# design.net
KiCad netlist of a schematic drawn in EAGLE
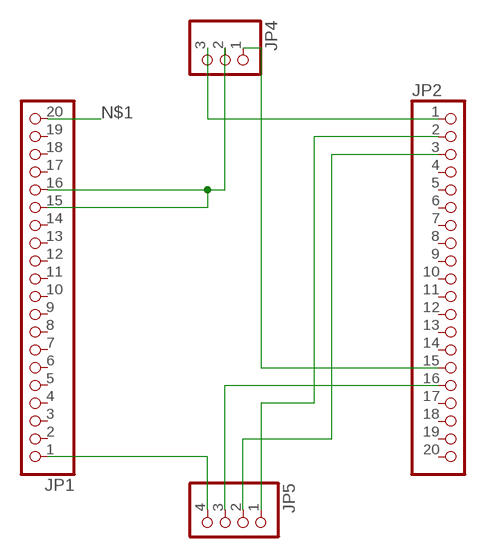
[diagram p0: schematic, sheet 1]

(export (version "E")
  (design (tool "Eeschema 10.0.6"))
  (components
    (comp (ref "JP1")
      (value "PINHD-1X20")
      (footprint "eagle-import:1X20")
      (libsource (lib "eagle-import") (part "PINHD-1X20"))
    )
    (comp (ref "JP2")
      (value "PINHD-1X20")
      (footprint "eagle-import:1X20")
      (libsource (lib "eagle-import") (part "PINHD-1X20"))
    )
    (comp (ref "JP4")
      (value "PINHD-1X3")
      (footprint "eagle-import:1X03")
      (libsource (lib "eagle-import") (part "PINHD-1X3"))
    )
    (comp (ref "JP5")
      (value "PINHD-1X4")
      (footprint "eagle-import:1X04")
      (libsource (lib "eagle-import") (part "PINHD-1X4"))
    )
  )
  (nets
    (net (code "1") (name "/N$1") (class "Default")
      (node (ref "JP1") (pin "20") (pinfunction "20_20") (pintype "passive"))
    )
    (net (code "2") (name "Net-(JP1-Pad1)") (class "Default")
      (node (ref "JP1") (pin "1") (pinfunction "1_1") (pintype "passive"))
      (node (ref "JP5") (pin "4") (pinfunction "4_4") (pintype "passive"))
    )
    (net (code "3") (name "Net-(JP1-Pad15)") (class "Default")
      (node (ref "JP1") (pin "15") (pinfunction "15_15") (pintype "passive"))
      (node (ref "JP1") (pin "16") (pinfunction "16_16") (pintype "passive"))
      (node (ref "JP4") (pin "2") (pinfunction "2_2") (pintype "passive"))
    )
    (net (code "4") (name "Net-(JP2-Pad1)") (class "Default")
      (node (ref "JP2") (pin "1") (pinfunction "1_1") (pintype "passive"))
      (node (ref "JP4") (pin "3") (pinfunction "3_3") (pintype "passive"))
    )
    (net (code "5") (name "Net-(JP2-Pad2)") (class "Default")
      (node (ref "JP2") (pin "2") (pinfunction "2_2") (pintype "passive"))
      (node (ref "JP5") (pin "1") (pinfunction "1_1") (pintype "passive"))
    )
    (net (code "6") (name "Net-(JP2-Pad3)") (class "Default")
      (node (ref "JP2") (pin "3") (pinfunction "3_3") (pintype "passive"))
      (node (ref "JP5") (pin "2") (pinfunction "2_2") (pintype "passive"))
    )
    (net (code "7") (name "Net-(JP2-Pad15)") (class "Default")
      (node (ref "JP2") (pin "15") (pinfunction "15_15") (pintype "passive"))
      (node (ref "JP4") (pin "1") (pinfunction "1_1") (pintype "passive"))
    )
    (net (code "8") (name "Net-(JP2-Pad16)") (class "Default")
      (node (ref "JP2") (pin "16") (pinfunction "16_16") (pintype "passive"))
      (node (ref "JP5") (pin "3") (pinfunction "3_3") (pintype "passive"))
    )
    (net (code "9") (name "unconnected-(JP1-Pad2)") (class "Default")
      (node (ref "JP1") (pin "2") (pinfunction "2_2") (pintype "passive"))
    )
    (net (code "10") (name "unconnected-(JP1-Pad3)") (class "Default")
      (node (ref "JP1") (pin "3") (pinfunction "3_3") (pintype "passive"))
    )
    (net (code "11") (name "unconnected-(JP1-Pad4)") (class "Default")
      (node (ref "JP1") (pin "4") (pinfunction "4_4") (pintype "passive"))
    )
    (net (code "12") (name "unconnected-(JP1-Pad5)") (class "Default")
      (node (ref "JP1") (pin "5") (pinfunction "5_5") (pintype "passive"))
    )
    (net (code "13") (name "unconnected-(JP1-Pad6)") (class "Default")
      (node (ref "JP1") (pin "6") (pinfunction "6_6") (pintype "passive"))
    )
    (net (code "14") (name "unconnected-(JP1-Pad7)") (class "Default")
      (node (ref "JP1") (pin "7") (pinfunction "7_7") (pintype "passive"))
    )
    (net (code "15") (name "unconnected-(JP1-Pad8)") (class "Default")
      (node (ref "JP1") (pin "8") (pinfunction "8_8") (pintype "passive"))
    )
    (net (code "16") (name "unconnected-(JP1-Pad9)") (class "Default")
      (node (ref "JP1") (pin "9") (pinfunction "9_9") (pintype "passive"))
    )
    (net (code "17") (name "unconnected-(JP1-Pad10)") (class "Default")
      (node (ref "JP1") (pin "10") (pinfunction "10_10") (pintype "passive"))
    )
    (net (code "18") (name "unconnected-(JP1-Pad11)") (class "Default")
      (node (ref "JP1") (pin "11") (pinfunction "11_11") (pintype "passive"))
    )
    (net (code "19") (name "unconnected-(JP1-Pad12)") (class "Default")
      (node (ref "JP1") (pin "12") (pinfunction "12_12") (pintype "passive"))
    )
    (net (code "20") (name "unconnected-(JP1-Pad13)") (class "Default")
      (node (ref "JP1") (pin "13") (pinfunction "13_13") (pintype "passive"))
    )
    (net (code "21") (name "unconnected-(JP1-Pad14)") (class "Default")
      (node (ref "JP1") (pin "14") (pinfunction "14_14") (pintype "passive"))
    )
    (net (code "22") (name "unconnected-(JP1-Pad17)") (class "Default")
      (node (ref "JP1") (pin "17") (pinfunction "17_17") (pintype "passive"))
    )
    (net (code "23") (name "unconnected-(JP1-Pad18)") (class "Default")
      (node (ref "JP1") (pin "18") (pinfunction "18_18") (pintype "passive"))
    )
    (net (code "24") (name "unconnected-(JP1-Pad19)") (class "Default")
      (node (ref "JP1") (pin "19") (pinfunction "19_19") (pintype "passive"))
    )
    (net (code "25") (name "unconnected-(JP2-Pad4)") (class "Default")
      (node (ref "JP2") (pin "4") (pinfunction "4_4") (pintype "passive"))
    )
    (net (code "26") (name "unconnected-(JP2-Pad5)") (class "Default")
      (node (ref "JP2") (pin "5") (pinfunction "5_5") (pintype "passive"))
    )
    (net (code "27") (name "unconnected-(JP2-Pad6)") (class "Default")
      (node (ref "JP2") (pin "6") (pinfunction "6_6") (pintype "passive"))
    )
    (net (code "28") (name "unconnected-(JP2-Pad7)") (class "Default")
      (node (ref "JP2") (pin "7") (pinfunction "7_7") (pintype "passive"))
    )
    (net (code "29") (name "unconnected-(JP2-Pad8)") (class "Default")
      (node (ref "JP2") (pin "8") (pinfunction "8_8") (pintype "passive"))
    )
    (net (code "30") (name "unconnected-(JP2-Pad9)") (class "Default")
      (node (ref "JP2") (pin "9") (pinfunction "9_9") (pintype "passive"))
    )
    (net (code "31") (name "unconnected-(JP2-Pad10)") (class "Default")
      (node (ref "JP2") (pin "10") (pinfunction "10_10") (pintype "passive"))
    )
    (net (code "32") (name "unconnected-(JP2-Pad11)") (class "Default")
      (node (ref "JP2") (pin "11") (pinfunction "11_11") (pintype "passive"))
    )
    (net (code "33") (name "unconnected-(JP2-Pad12)") (class "Default")
      (node (ref "JP2") (pin "12") (pinfunction "12_12") (pintype "passive"))
    )
    (net (code "34") (name "unconnected-(JP2-Pad13)") (class "Default")
      (node (ref "JP2") (pin "13") (pinfunction "13_13") (pintype "passive"))
    )
    (net (code "35") (name "unconnected-(JP2-Pad14)") (class "Default")
      (node (ref "JP2") (pin "14") (pinfunction "14_14") (pintype "passive"))
    )
    (net (code "36") (name "unconnected-(JP2-Pad17)") (class "Default")
      (node (ref "JP2") (pin "17") (pinfunction "17_17") (pintype "passive"))
    )
    (net (code "37") (name "unconnected-(JP2-Pad18)") (class "Default")
      (node (ref "JP2") (pin "18") (pinfunction "18_18") (pintype "passive"))
    )
    (net (code "38") (name "unconnected-(JP2-Pad19)") (class "Default")
      (node (ref "JP2") (pin "19") (pinfunction "19_19") (pintype "passive"))
    )
    (net (code "39") (name "unconnected-(JP2-Pad20)") (class "Default")
      (node (ref "JP2") (pin "20") (pinfunction "20_20") (pintype "passive"))
    )
  )
)
